# HTH-2019-Badge-PROD-RC1.net
KiCad netlist of a schematic drawn in EAGLE
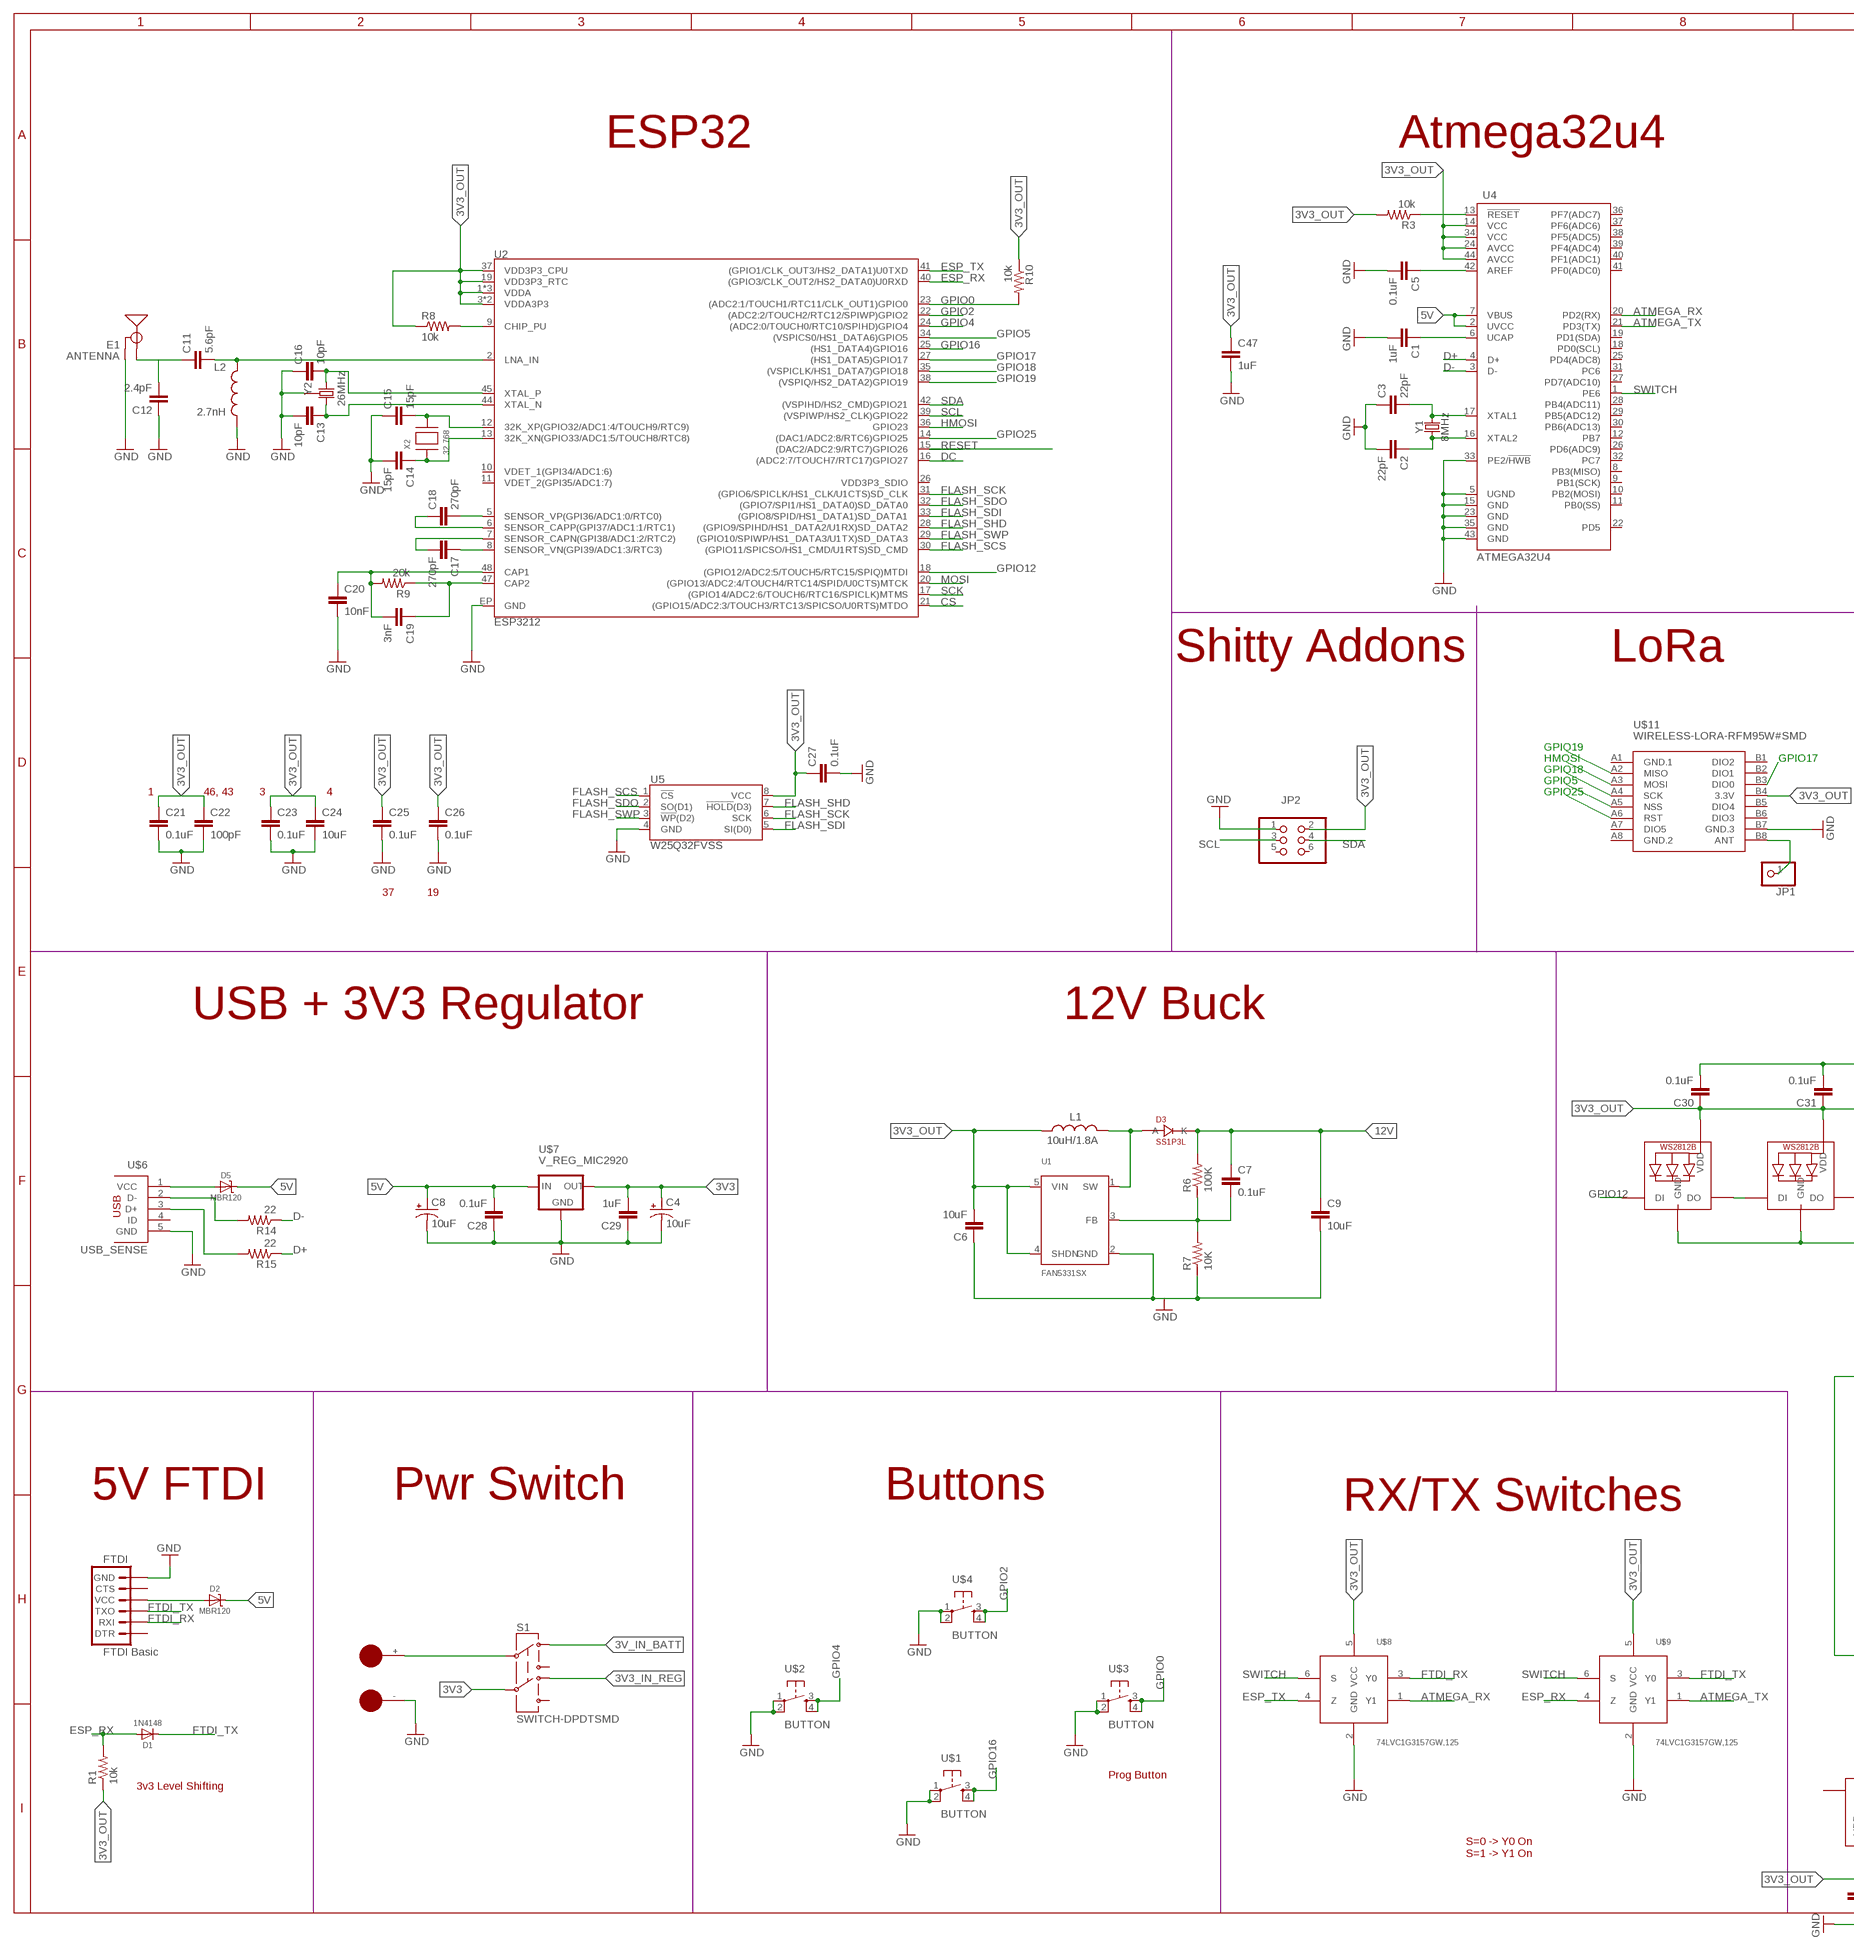
[diagram p0: schematic, sheet 1, part 1 of 2]
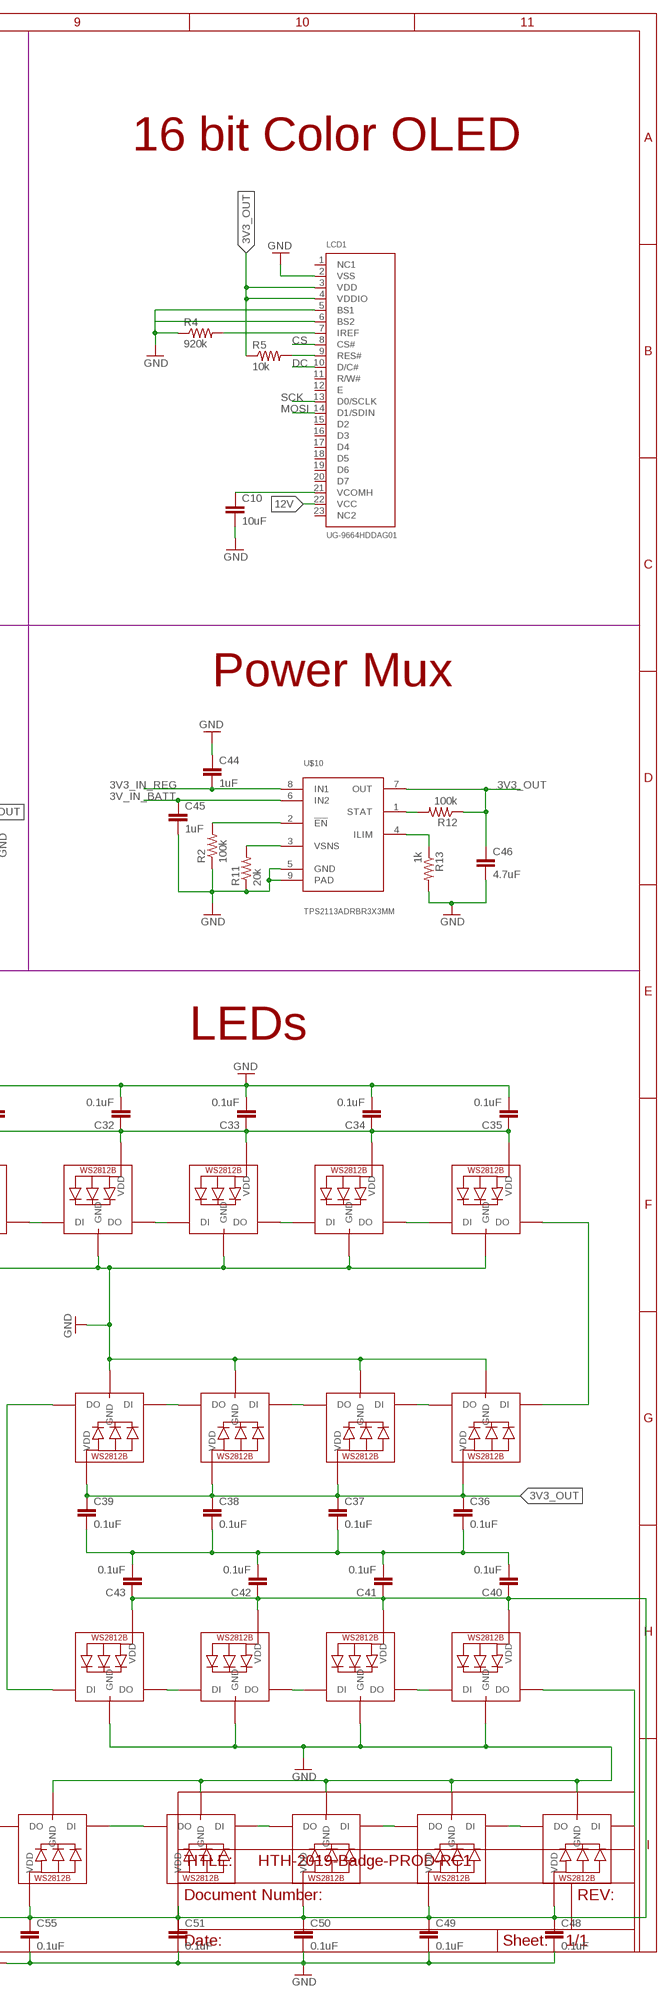
[diagram p1: schematic, sheet 1, part 2 of 2]

(export (version "E")
  (design (tool "Eeschema 10.0.6"))
  (components
    (comp (ref "C1")
      (value "1uF")
      (footprint "eagle-import:CAP0603")
      (libsource (lib "eagle-import") (part "CAP-0603-EMPTY-VALUES"))
    )
    (comp (ref "C2")
      (value "22pF")
      (footprint "eagle-import:CAP0603")
      (libsource (lib "eagle-import") (part "CAP-0603-EMPTY-VALUES"))
    )
    (comp (ref "C3")
      (value "22pF")
      (footprint "eagle-import:CAP0603")
      (libsource (lib "eagle-import") (part "CAP-0603-EMPTY-VALUES"))
    )
    (comp (ref "C4")
      (value "10uF")
      (footprint "eagle-import:EIA3216")
      (libsource (lib "eagle-import") (part "CAP_POL1206"))
    )
    (comp (ref "C5")
      (value "0.1uF")
      (footprint "eagle-import:CAP0603")
      (libsource (lib "eagle-import") (part "CAP-0603-EMPTY-VALUES"))
    )
    (comp (ref "C6")
      (value "10uF")
      (footprint "eagle-import:CAP0603")
      (fields (field (name "TOLERANCE") "10%") (field (name "VOLTAGE") "10V"))
      (libsource (lib "eagle-import") (part "CAP-0603-10UF-10V-10%"))
    )
    (comp (ref "C7")
      (value "0.1uF")
      (footprint "eagle-import:CAP0603")
      (fields (field (name "TOLERANCE") "10%") (field (name "VOLTAGE") "25V"))
      (libsource (lib "eagle-import") (part "CAP-0603-0.1UF-25V-10%"))
    )
    (comp (ref "C8")
      (value "10uF")
      (footprint "eagle-import:EIA3216")
      (libsource (lib "eagle-import") (part "CAP_POL1206"))
    )
    (comp (ref "C9")
      (value "10uF")
      (footprint "eagle-import:CAP0603")
      (fields (field (name "TOLERANCE") "20%") (field (name "VOLTAGE") "25V"))
      (libsource (lib "eagle-import") (part "CAP-0603-10UF-25V-20%"))
    )
    (comp (ref "C10")
      (value "10uF")
      (footprint "eagle-import:CAP0603")
      (libsource (lib "eagle-import") (part "CAP-0603-EMPTY-VALUES"))
    )
    (comp (ref "C11")
      (value "5.6pF")
      (footprint "eagle-import:CAP0603")
      (libsource (lib "eagle-import") (part "CAP-0603-EMPTY-VALUES"))
    )
    (comp (ref "C12")
      (value "2.4pF")
      (footprint "eagle-import:CAP0603")
      (libsource (lib "eagle-import") (part "CAP-0603-EMPTY-VALUES"))
    )
    (comp (ref "C13")
      (value "10pF")
      (footprint "eagle-import:CAP0603")
      (libsource (lib "eagle-import") (part "CAP-0603-EMPTY-VALUES"))
    )
    (comp (ref "C14")
      (value "15pF")
      (footprint "eagle-import:CAP0603")
      (libsource (lib "eagle-import") (part "CAP-0603-EMPTY-VALUES"))
    )
    (comp (ref "C15")
      (value "15pF")
      (footprint "eagle-import:CAP0603")
      (libsource (lib "eagle-import") (part "CAP-0603-EMPTY-VALUES"))
    )
    (comp (ref "C16")
      (value "10pF")
      (footprint "eagle-import:CAP0603")
      (libsource (lib "eagle-import") (part "CAP-0603-EMPTY-VALUES"))
    )
    (comp (ref "C17")
      (value "270pF")
      (footprint "eagle-import:CAP0603")
      (libsource (lib "eagle-import") (part "CAP-0603-EMPTY-VALUES"))
    )
    (comp (ref "C18")
      (value "270pF")
      (footprint "eagle-import:CAP0603")
      (libsource (lib "eagle-import") (part "CAP-0603-EMPTY-VALUES"))
    )
    (comp (ref "C19")
      (value "3nF")
      (footprint "eagle-import:CAP0603")
      (libsource (lib "eagle-import") (part "CAP-0603-EMPTY-VALUES"))
    )
    (comp (ref "C20")
      (value "10nF")
      (footprint "eagle-import:CAP0603")
      (libsource (lib "eagle-import") (part "CAP-0603-EMPTY-VALUES"))
    )
    (comp (ref "C21")
      (value "0.1uF")
      (footprint "eagle-import:CAP0603")
      (libsource (lib "eagle-import") (part "CAP-0603-EMPTY-VALUES"))
    )
    (comp (ref "C22")
      (value "100pF")
      (footprint "eagle-import:CAP0603")
      (libsource (lib "eagle-import") (part "CAP-0603-EMPTY-VALUES"))
    )
    (comp (ref "C23")
      (value "0.1uF")
      (footprint "eagle-import:CAP0603")
      (libsource (lib "eagle-import") (part "CAP-0603-EMPTY-VALUES"))
    )
    (comp (ref "C24")
      (value "10uF")
      (footprint "eagle-import:CAP0603")
      (libsource (lib "eagle-import") (part "CAP-0603-EMPTY-VALUES"))
    )
    (comp (ref "C25")
      (value "0.1uF")
      (footprint "eagle-import:CAP0603")
      (libsource (lib "eagle-import") (part "CAP-0603-EMPTY-VALUES"))
    )
    (comp (ref "C26")
      (value "0.1uF")
      (footprint "eagle-import:CAP0603")
      (libsource (lib "eagle-import") (part "CAP-0603-EMPTY-VALUES"))
    )
    (comp (ref "C27")
      (value "0.1uF")
      (footprint "eagle-import:CAP0603")
      (libsource (lib "eagle-import") (part "CAP-0603-EMPTY-VALUES"))
    )
    (comp (ref "C28")
      (value "0.1uF")
      (footprint "eagle-import:CAP0603")
      (libsource (lib "eagle-import") (part "CAP-0603-EMPTY-VALUES"))
    )
    (comp (ref "C29")
      (value "1uF")
      (footprint "eagle-import:CAP0603")
      (libsource (lib "eagle-import") (part "CAP-0603-EMPTY-VALUES"))
    )
    (comp (ref "C30")
      (value "0.1uF")
      (footprint "eagle-import:CAP0603")
      (libsource (lib "eagle-import") (part "CAP-0603-EMPTY-VALUES"))
    )
    (comp (ref "C31")
      (value "0.1uF")
      (footprint "eagle-import:CAP0603")
      (libsource (lib "eagle-import") (part "CAP-0603-EMPTY-VALUES"))
    )
    (comp (ref "C32")
      (value "0.1uF")
      (footprint "eagle-import:CAP0603")
      (libsource (lib "eagle-import") (part "CAP-0603-EMPTY-VALUES"))
    )
    (comp (ref "C33")
      (value "0.1uF")
      (footprint "eagle-import:CAP0603")
      (libsource (lib "eagle-import") (part "CAP-0603-EMPTY-VALUES"))
    )
    (comp (ref "C34")
      (value "0.1uF")
      (footprint "eagle-import:CAP0603")
      (libsource (lib "eagle-import") (part "CAP-0603-EMPTY-VALUES"))
    )
    (comp (ref "C35")
      (value "0.1uF")
      (footprint "eagle-import:CAP0603")
      (libsource (lib "eagle-import") (part "CAP-0603-EMPTY-VALUES"))
    )
    (comp (ref "C36")
      (value "0.1uF")
      (footprint "eagle-import:CAP0603")
      (libsource (lib "eagle-import") (part "CAP-0603-EMPTY-VALUES"))
    )
    (comp (ref "C37")
      (value "0.1uF")
      (footprint "eagle-import:CAP0603")
      (libsource (lib "eagle-import") (part "CAP-0603-EMPTY-VALUES"))
    )
    (comp (ref "C38")
      (value "0.1uF")
      (footprint "eagle-import:CAP0603")
      (libsource (lib "eagle-import") (part "CAP-0603-EMPTY-VALUES"))
    )
    (comp (ref "C39")
      (value "0.1uF")
      (footprint "eagle-import:CAP0603")
      (libsource (lib "eagle-import") (part "CAP-0603-EMPTY-VALUES"))
    )
    (comp (ref "C40")
      (value "0.1uF")
      (footprint "eagle-import:CAP0603")
      (libsource (lib "eagle-import") (part "CAP-0603-EMPTY-VALUES"))
    )
    (comp (ref "C41")
      (value "0.1uF")
      (footprint "eagle-import:CAP0603")
      (libsource (lib "eagle-import") (part "CAP-0603-EMPTY-VALUES"))
    )
    (comp (ref "C42")
      (value "0.1uF")
      (footprint "eagle-import:CAP0603")
      (libsource (lib "eagle-import") (part "CAP-0603-EMPTY-VALUES"))
    )
    (comp (ref "C43")
      (value "0.1uF")
      (footprint "eagle-import:CAP0603")
      (libsource (lib "eagle-import") (part "CAP-0603-EMPTY-VALUES"))
    )
    (comp (ref "C44")
      (value "1uF")
      (footprint "eagle-import:CAP0603")
      (libsource (lib "eagle-import") (part "CAP-0603-EMPTY-VALUES"))
    )
    (comp (ref "C45")
      (value "1uF")
      (footprint "eagle-import:CAP0603")
      (libsource (lib "eagle-import") (part "CAP-0603-EMPTY-VALUES"))
    )
    (comp (ref "C46")
      (value "4.7uF")
      (footprint "eagle-import:CAP0603")
      (libsource (lib "eagle-import") (part "CAP-0603-EMPTY-VALUES"))
    )
    (comp (ref "C47")
      (value "1uF")
      (footprint "eagle-import:CAP0603")
      (libsource (lib "eagle-import") (part "CAP-0603-EMPTY-VALUES"))
    )
    (comp (ref "C48")
      (value "0.1uF")
      (footprint "eagle-import:CAP0603")
      (libsource (lib "eagle-import") (part "CAP-0603-EMPTY-VALUES"))
    )
    (comp (ref "C49")
      (value "0.1uF")
      (footprint "eagle-import:CAP0603")
      (libsource (lib "eagle-import") (part "CAP-0603-EMPTY-VALUES"))
    )
    (comp (ref "C50")
      (value "0.1uF")
      (footprint "eagle-import:CAP0603")
      (libsource (lib "eagle-import") (part "CAP-0603-EMPTY-VALUES"))
    )
    (comp (ref "C51")
      (value "0.1uF")
      (footprint "eagle-import:CAP0603")
      (libsource (lib "eagle-import") (part "CAP-0603-EMPTY-VALUES"))
    )
    (comp (ref "C55")
      (value "0.1uF")
      (footprint "eagle-import:CAP0603")
      (libsource (lib "eagle-import") (part "CAP-0603-EMPTY-VALUES"))
    )
    (comp (ref "D1")
      (value "1N4148")
      (footprint "eagle-import:SOD-323")
      (libsource (lib "eagle-import") (part "DIODESOD-323"))
    )
    (comp (ref "D2")
      (value "MBR120")
      (footprint "eagle-import:SOD-123")
      (libsource (lib "eagle-import") (part "DIODE-SCHOTTKYSOD-123"))
    )
    (comp (ref "D3")
      (value "SS1P3L")
      (footprint "eagle-import:DO220AAL")
      (libsource (lib "eagle-import") (part "SS1P3L"))
    )
    (comp (ref "D5")
      (value "MBR120")
      (footprint "eagle-import:SOD-123")
      (libsource (lib "eagle-import") (part "DIODE-SCHOTTKYSOD-123"))
    )
    (comp (ref "E1")
      (value "ANTENNA")
      (footprint "eagle-import:TRACE_ANTENNA_2.4GHZ_25.7MM_TUNED")
      (libsource (lib "eagle-import") (part "ANTENNATRACE-TUNED"))
    )
    (comp (ref "FTDI")
      (value "FTDI Basic")
      (footprint "eagle-import:1X06")
      (libsource (lib "eagle-import") (part "ARDUINO_SERIAL_PROGRAMPTH"))
    )
    (comp (ref "JP1")
      (value "PINHD-1X1")
      (footprint "eagle-import:1X01")
      (libsource (lib "eagle-import") (part "PINHD-1X1"))
    )
    (comp (ref "JP2")
      (value "PINHD-2X3")
      (footprint "eagle-import:2X03")
      (libsource (lib "eagle-import") (part "PINHD-2X3"))
    )
    (comp (ref "L1")
      (value "10uH/1.8A")
      (footprint "eagle-import:SRU5028")
      (libsource (lib "eagle-import") (part "INDUCTORSRU5028"))
    )
    (comp (ref "L2")
      (value "2.7nH")
      (footprint "eagle-import:0603")
      (libsource (lib "eagle-import") (part "SparkFun-Passives_INDUCTOR0603"))
    )
    (comp (ref "LCD1")
      (value "UG-9664HDDAG01")
      (footprint "eagle-import:UG-9664HDDAG01_WRAPAROUND")
      (libsource (lib "eagle-import") (part "DISP_OLED_UG-9664HDDAG01WRAPAROUND"))
    )
    (comp (ref "LED1")
      (value "WS2812B3535")
      (footprint "eagle-import:LED3535")
      (libsource (lib "eagle-import") (part "WS2812B3535"))
    )
    (comp (ref "LED2")
      (value "WS2812B3535")
      (footprint "eagle-import:LED3535")
      (libsource (lib "eagle-import") (part "WS2812B3535"))
    )
    (comp (ref "LED3")
      (value "WS2812B3535")
      (footprint "eagle-import:LED3535")
      (libsource (lib "eagle-import") (part "WS2812B3535"))
    )
    (comp (ref "LED4")
      (value "WS2812B3535")
      (footprint "eagle-import:LED3535")
      (libsource (lib "eagle-import") (part "WS2812B3535"))
    )
    (comp (ref "LED5")
      (value "WS2812B3535")
      (footprint "eagle-import:LED3535")
      (libsource (lib "eagle-import") (part "WS2812B3535"))
    )
    (comp (ref "LED6")
      (value "WS2812B3535")
      (footprint "eagle-import:LED3535")
      (libsource (lib "eagle-import") (part "WS2812B3535"))
    )
    (comp (ref "LED7")
      (value "WS2812B3535")
      (footprint "eagle-import:LED3535")
      (libsource (lib "eagle-import") (part "WS2812B3535"))
    )
    (comp (ref "LED8")
      (value "WS2812B3535")
      (footprint "eagle-import:LED3535")
      (libsource (lib "eagle-import") (part "WS2812B3535"))
    )
    (comp (ref "LED9")
      (value "WS2812B3535")
      (footprint "eagle-import:LED3535")
      (libsource (lib "eagle-import") (part "WS2812B3535"))
    )
    (comp (ref "LED10")
      (value "WS2812B3535")
      (footprint "eagle-import:LED3535")
      (libsource (lib "eagle-import") (part "WS2812B3535"))
    )
    (comp (ref "LED11")
      (value "WS2812B3535")
      (footprint "eagle-import:LED3535")
      (libsource (lib "eagle-import") (part "WS2812B3535"))
    )
    (comp (ref "LED12")
      (value "WS2812B3535")
      (footprint "eagle-import:LED3535")
      (libsource (lib "eagle-import") (part "WS2812B3535"))
    )
    (comp (ref "LED13")
      (value "WS2812B3535")
      (footprint "eagle-import:LED3535")
      (libsource (lib "eagle-import") (part "WS2812B3535"))
    )
    (comp (ref "LED14")
      (value "WS2812B3535")
      (footprint "eagle-import:LED3535")
      (libsource (lib "eagle-import") (part "WS2812B3535"))
    )
    (comp (ref "LED15")
      (value "WS2812B3535")
      (footprint "eagle-import:LED3535")
      (libsource (lib "eagle-import") (part "WS2812B3535"))
    )
    (comp (ref "LED16")
      (value "WS2812B3535")
      (footprint "eagle-import:LED3535")
      (libsource (lib "eagle-import") (part "WS2812B3535"))
    )
    (comp (ref "LED17")
      (value "WS2812B3535")
      (footprint "eagle-import:LED3535")
      (libsource (lib "eagle-import") (part "WS2812B3535"))
    )
    (comp (ref "LED18")
      (value "WS2812B3535")
      (footprint "eagle-import:LED3535")
      (libsource (lib "eagle-import") (part "WS2812B3535"))
    )
    (comp (ref "LED19")
      (value "WS2812B3535")
      (footprint "eagle-import:LED3535")
      (libsource (lib "eagle-import") (part "WS2812B3535"))
    )
    (comp (ref "R1")
      (value "10k")
      (footprint "eagle-import:RES-0603")
      (libsource (lib "eagle-import") (part "RES-0603_EMPTY-FIELDS"))
    )
    (comp (ref "R2")
      (value "100k")
      (footprint "eagle-import:RES-0603")
      (libsource (lib "eagle-import") (part "RES-0603_EMPTY-FIELDS"))
    )
    (comp (ref "R3")
      (value "10k")
      (footprint "eagle-import:RES-0603")
      (libsource (lib "eagle-import") (part "RES-0603_EMPTY-FIELDS"))
    )
    (comp (ref "R4")
      (value "920k")
      (footprint "eagle-import:RES-0603")
      (libsource (lib "eagle-import") (part "RES-0603_EMPTY-FIELDS"))
    )
    (comp (ref "R5")
      (value "10k")
      (footprint "eagle-import:RES-0603")
      (libsource (lib "eagle-import") (part "RES-0603_EMPTY-FIELDS"))
    )
    (comp (ref "R6")
      (value "100K")
      (footprint "eagle-import:RES-0603")
      (fields (field (name "TOLERANCE") "5%"))
      (libsource (lib "eagle-import") (part "RES-0603-100K-5%"))
    )
    (comp (ref "R7")
      (value "10K")
      (footprint "eagle-import:RES-0603")
      (fields (field (name "TOLERANCE") "5%"))
      (libsource (lib "eagle-import") (part "RES-0603-10K-5%"))
    )
    (comp (ref "R8")
      (value "10k")
      (footprint "eagle-import:RES-0603")
      (libsource (lib "eagle-import") (part "RES-0603_EMPTY-FIELDS"))
    )
    (comp (ref "R9")
      (value "20k")
      (footprint "eagle-import:RES-0603")
      (libsource (lib "eagle-import") (part "RES-0603_EMPTY-FIELDS"))
    )
    (comp (ref "R10")
      (value "10k")
      (footprint "eagle-import:RES-0603")
      (libsource (lib "eagle-import") (part "RES-0603_EMPTY-FIELDS"))
    )
    (comp (ref "R11")
      (value "20k")
      (footprint "eagle-import:RES-0603")
      (libsource (lib "eagle-import") (part "RES-0603_EMPTY-FIELDS"))
    )
    (comp (ref "R12")
      (value "100k")
      (footprint "eagle-import:RES-0603")
      (libsource (lib "eagle-import") (part "RES-0603_EMPTY-FIELDS"))
    )
    (comp (ref "R13")
      (value "1k")
      (footprint "eagle-import:RES-0603")
      (libsource (lib "eagle-import") (part "RES-0603_EMPTY-FIELDS"))
    )
    (comp (ref "R14")
      (value "22")
      (footprint "eagle-import:RES-0603")
      (libsource (lib "eagle-import") (part "RES-0603_EMPTY-FIELDS"))
    )
    (comp (ref "R15")
      (value "22")
      (footprint "eagle-import:RES-0603")
      (libsource (lib "eagle-import") (part "RES-0603_EMPTY-FIELDS"))
    )
    (comp (ref "S1")
      (value "SWITCH-DPDTSMD")
      (footprint "eagle-import:AYZ0202")
      (libsource (lib "eagle-import") (part "SWITCH-DPDTSMD"))
    )
    (comp (ref "U$1")
      (value "BUTTON")
      (footprint "eagle-import:BUTTON")
      (libsource (lib "eagle-import") (part "BUTTON"))
    )
    (comp (ref "U$2")
      (value "BUTTON")
      (footprint "eagle-import:BUTTON")
      (libsource (lib "eagle-import") (part "BUTTON"))
    )
    (comp (ref "U$3")
      (value "BUTTON")
      (footprint "eagle-import:BUTTON")
      (libsource (lib "eagle-import") (part "BUTTON"))
    )
    (comp (ref "U$4")
      (value "BUTTON")
      (footprint "eagle-import:BUTTON")
      (libsource (lib "eagle-import") (part "BUTTON"))
    )
    (comp (ref "U$5")
      (value "BAT_HOLD")
      (footprint "eagle-import:AA")
      (libsource (lib "eagle-import") (part "BAT_HOLD"))
    )
    (comp (ref "U$6")
      (value "USB_SENSE")
      (footprint "eagle-import:USB-MICRO-TH-SUPPORT")
      (libsource (lib "eagle-import") (part "USB_SENSE"))
    )
    (comp (ref "U$7")
      (value "V_REG_MIC2920")
      (footprint "eagle-import:SOT223")
      (libsource (lib "eagle-import") (part "V_REG_MIC2920"))
    )
    (comp (ref "U$8")
      (value "74LVC1G3157GW,125")
      (footprint "eagle-import:SOT-363")
      (libsource (lib "eagle-import") (part "74LVC1G3157GW,125"))
    )
    (comp (ref "U$9")
      (value "74LVC1G3157GW,125")
      (footprint "eagle-import:SOT-363")
      (libsource (lib "eagle-import") (part "74LVC1G3157GW,125"))
    )
    (comp (ref "U$10")
      (value "TPS2113ADRBR3X3MM")
      (footprint "eagle-import:8-VDFN")
      (libsource (lib "eagle-import") (part "TPS2113ADRBR3X3MM"))
    )
    (comp (ref "U$11")
      (value "WIRELESS-LORA-RFM95W#SMD")
      (footprint "eagle-import:WIRELESS-LORA-RFM95W#SMD")
      (libsource (lib "eagle-import") (part "WIRELESS-LORA-RFM95W#SMD"))
    )
    (comp (ref "U1")
      (value "FAN5331SX")
      (footprint "eagle-import:SOT23-5")
      (libsource (lib "eagle-import") (part "FAN5331"))
    )
    (comp (ref "U2")
      (value "ESP3212")
      (footprint "eagle-import:QFN48-0.4MM")
      (libsource (lib "eagle-import") (part "ESP3212"))
    )
    (comp (ref "U4")
      (value "ATMEGA32U4")
      (footprint "eagle-import:QFN-44-NOPAD_1_1-OUTFAKES")
      (libsource (lib "eagle-import") (part "ATMEGA32U4OUTFAKES"))
    )
    (comp (ref "U5")
      (value "W25Q32FVSS")
      (footprint "eagle-import:SOIC-8")
      (libsource (lib "eagle-import") (part "W25Q32FVSS"))
    )
    (comp (ref "X2")
      (value "32.768")
      (footprint "eagle-import:XTAL3215")
      (libsource (lib "eagle-import") (part "XTAL-3.2X1.5"))
    )
    (comp (ref "Y1")
      (value "8MHz")
      (footprint "eagle-import:CRYSTAL-SMD-5X3.2-4PAD")
      (libsource (lib "eagle-import") (part "CRYSTAL-8MHZSMD-5X3.2"))
    )
    (comp (ref "Y2")
      (value "26MHz")
      (footprint "eagle-import:CRYSTAL-SMD-3.2X2.5")
      (libsource (lib "eagle-import") (part "CRYSTAL-GROUNDED3.2X2.5"))
    )
  )
  (nets
    (net (code "1") (name "/ATMEGA_RX") (class "Default")
      (node (ref "U$8") (pin "1") (pinfunction "Y1_1") (pintype "bidirectional"))
      (node (ref "U4") (pin "20") (pinfunction "PD2(RX)_20") (pintype "bidirectional"))
    )
    (net (code "2") (name "/ATMEGA_TX") (class "Default")
      (node (ref "U$9") (pin "1") (pinfunction "Y1_1") (pintype "bidirectional"))
      (node (ref "U4") (pin "21") (pinfunction "PD3(TX)_21") (pintype "bidirectional"))
    )
    (net (code "3") (name "/CS") (class "Default")
      (node (ref "LCD1") (pin "8") (pinfunction "CS#_8") (pintype "bidirectional"))
      (node (ref "U2") (pin "21") (pinfunction "(GPIO15/ADC2:3/TOUCH3/RTC13/SPICSO/U0RTS)MTDO_21") (pintype "bidirectional"))
    )
    (net (code "4") (name "/D+") (class "Default")
      (node (ref "R15") (pin "1") (pinfunction "1_1") (pintype "passive"))
      (node (ref "U4") (pin "4") (pinfunction "D+_4") (pintype "bidirectional"))
    )
    (net (code "5") (name "/D-") (class "Default")
      (node (ref "R14") (pin "1") (pinfunction "1_1") (pintype "passive"))
      (node (ref "U4") (pin "3") (pinfunction "D-_3") (pintype "bidirectional"))
    )
    (net (code "6") (name "/DC") (class "Default")
      (node (ref "LCD1") (pin "10") (pinfunction "D/C#_10") (pintype "bidirectional"))
      (node (ref "U2") (pin "16") (pinfunction "(ADC2:7/TOUCH7/RTC17)GPIO27_16") (pintype "bidirectional"))
    )
    (net (code "7") (name "/ESP_RX") (class "Default")
      (node (ref "D1") (pin "A") (pinfunction "A_A") (pintype "passive"))
      (node (ref "R1") (pin "2") (pinfunction "2_2") (pintype "passive"))
      (node (ref "U$9") (pin "4") (pinfunction "Z_4") (pintype "bidirectional"))
      (node (ref "U2") (pin "40") (pinfunction "(GPIO3/CLK_OUT2/HS2_DATA0)U0RXD_40") (pintype "bidirectional"))
    )
    (net (code "8") (name "/ESP_TX") (class "Default")
      (node (ref "U$8") (pin "4") (pinfunction "Z_4") (pintype "bidirectional"))
      (node (ref "U2") (pin "41") (pinfunction "(GPIO1/CLK_OUT3/HS2_DATA1)U0TXD_41") (pintype "bidirectional"))
    )
    (net (code "9") (name "/FLASH_SCK") (class "Default")
      (node (ref "U2") (pin "31") (pinfunction "(GPIO6/SPICLK/HS1_CLK/U1CTS)SD_CLK_31") (pintype "bidirectional"))
      (node (ref "U5") (pin "6") (pinfunction "SCK_6") (pintype "bidirectional"))
    )
    (net (code "10") (name "/FLASH_SCS") (class "Default")
      (node (ref "U2") (pin "30") (pinfunction "(GPIO11/SPICSO/HS1_CMD/U1RTS)SD_CMD_30") (pintype "bidirectional"))
      (node (ref "U5") (pin "1") (pinfunction "~{CS}_1") (pintype "bidirectional"))
    )
    (net (code "11") (name "/FLASH_SDI") (class "Default")
      (node (ref "U2") (pin "33") (pinfunction "(GPIO8/SPID/HS1_DATA1)SD_DATA1_33") (pintype "bidirectional"))
      (node (ref "U5") (pin "5") (pinfunction "SI(D0)_5") (pintype "bidirectional"))
    )
    (net (code "12") (name "/FLASH_SDO") (class "Default")
      (node (ref "U2") (pin "32") (pinfunction "(GPIO7/SPI1/HS1_DATA0)SD_DATA0_32") (pintype "bidirectional"))
      (node (ref "U5") (pin "2") (pinfunction "SO(D1)_2") (pintype "bidirectional"))
    )
    (net (code "13") (name "/FLASH_SHD") (class "Default")
      (node (ref "U2") (pin "28") (pinfunction "(GPIO9/SPIHD/HS1_DATA2/U1RX)SD_DATA2_28") (pintype "bidirectional"))
      (node (ref "U5") (pin "7") (pinfunction "~{HOLD}(D3)_7") (pintype "bidirectional"))
    )
    (net (code "14") (name "/FLASH_SWP") (class "Default")
      (node (ref "U2") (pin "29") (pinfunction "(GPIO10/SPIWP/HS1_DATA3/U1TX)SD_DATA3_29") (pintype "bidirectional"))
      (node (ref "U5") (pin "3") (pinfunction "~{WP}(D2)_3") (pintype "bidirectional"))
    )
    (net (code "15") (name "/FTDI_RX") (class "Default")
      (node (ref "FTDI") (pin "2") (pinfunction "RXI_2") (pintype "passive"))
      (node (ref "U$8") (pin "3") (pinfunction "Y0_3") (pintype "bidirectional"))
    )
    (net (code "16") (name "/FTDI_TX") (class "Default")
      (node (ref "D1") (pin "C") (pinfunction "C_C") (pintype "passive"))
      (node (ref "FTDI") (pin "3") (pinfunction "TXO_3") (pintype "passive"))
      (node (ref "U$9") (pin "3") (pinfunction "Y0_3") (pintype "bidirectional"))
    )
    (net (code "17") (name "/GND.1") (class "Default")
      (node (ref "U$11") (pin "A1") (pinfunction "GND.1_A1") (pintype "power_in"))
    )
    (net (code "18") (name "/GND.2") (class "Default")
      (node (ref "U$11") (pin "A8") (pinfunction "GND.2_A8") (pintype "power_in"))
    )
    (net (code "19") (name "/GPIO0") (class "Default")
      (node (ref "R10") (pin "2") (pinfunction "2_2") (pintype "passive"))
      (node (ref "U$3") (pin "3") (pinfunction "3_3") (pintype "passive"))
      (node (ref "U$3") (pin "4") (pinfunction "4_4") (pintype "passive"))
      (node (ref "U2") (pin "23") (pinfunction "(ADC2:1/TOUCH1/RTC11/CLK_OUT1)GPIO0_23") (pintype "bidirectional"))
    )
    (net (code "20") (name "/GPIO2") (class "Default")
      (node (ref "U$4") (pin "3") (pinfunction "3_3") (pintype "passive"))
      (node (ref "U$4") (pin "4") (pinfunction "4_4") (pintype "passive"))
      (node (ref "U2") (pin "22") (pinfunction "(ADC2:2/TOUCH2/RTC12/SPIWP)GPIO2_22") (pintype "bidirectional"))
    )
    (net (code "21") (name "/GPIO4") (class "Default")
      (node (ref "U$2") (pin "3") (pinfunction "3_3") (pintype "passive"))
      (node (ref "U$2") (pin "4") (pinfunction "4_4") (pintype "passive"))
      (node (ref "U2") (pin "24") (pinfunction "(ADC2:0/TOUCH0/RTC10/SPIHD)GPIO4_24") (pintype "bidirectional"))
    )
    (net (code "22") (name "/GPIO5") (class "Default")
      (node (ref "U$11") (pin "A5") (pinfunction "NSS_A5") (pintype "bidirectional"))
      (node (ref "U2") (pin "34") (pinfunction "(VSPICS0/HS1_DATA6)GPIO5_34") (pintype "bidirectional"))
    )
    (net (code "23") (name "/GPIO12") (class "Default")
      (node (ref "LED5") (pin "1") (pinfunction "DI_1") (pintype "input"))
      (node (ref "U2") (pin "18") (pinfunction "(GPIO12/ADC2:5/TOUCH5/RTC15/SPIQ)MTDI_18") (pintype "bidirectional"))
    )
    (net (code "24") (name "/GPIO16") (class "Default")
      (node (ref "U$1") (pin "3") (pinfunction "3_3") (pintype "passive"))
      (node (ref "U$1") (pin "4") (pinfunction "4_4") (pintype "passive"))
      (node (ref "U2") (pin "25") (pinfunction "(HS1_DATA4)GPIO16_25") (pintype "bidirectional"))
    )
    (net (code "25") (name "/GPIO17") (class "Default")
      (node (ref "U$11") (pin "B3") (pinfunction "DIO0_B3") (pintype "bidirectional"))
      (node (ref "U2") (pin "27") (pinfunction "(HS1_DATA5)GPIO17_27") (pintype "bidirectional"))
    )
    (net (code "26") (name "/GPIO18") (class "Default")
      (node (ref "U$11") (pin "A4") (pinfunction "SCK_A4") (pintype "bidirectional"))
      (node (ref "U2") (pin "35") (pinfunction "(VSPICLK/HS1_DATA7)GPIO18_35") (pintype "bidirectional"))
    )
    (net (code "27") (name "/GPIO19") (class "Default")
      (node (ref "U$11") (pin "A2") (pinfunction "MISO_A2") (pintype "bidirectional"))
      (node (ref "U2") (pin "38") (pinfunction "(VSPIQ/HS2_DATA2)GPIO19_38") (pintype "bidirectional"))
    )
    (net (code "28") (name "/GPIO25") (class "Default")
      (node (ref "U$11") (pin "A6") (pinfunction "RST_A6") (pintype "bidirectional"))
      (node (ref "U2") (pin "14") (pinfunction "(DAC1/ADC2:8/RTC6)GPIO25_14") (pintype "bidirectional"))
    )
    (net (code "29") (name "/HMOSI") (class "Default")
      (node (ref "U$11") (pin "A3") (pinfunction "MOSI_A3") (pintype "bidirectional"))
      (node (ref "U2") (pin "36") (pinfunction "GPIO23_36") (pintype "bidirectional"))
    )
    (net (code "30") (name "/MOSI") (class "Default")
      (node (ref "LCD1") (pin "14") (pinfunction "D1/SDIN_14") (pintype "bidirectional"))
      (node (ref "U2") (pin "20") (pinfunction "(GPIO13/ADC2:4/TOUCH4/RTC14/SPID/U0CTS)MTCK_20") (pintype "bidirectional"))
    )
    (net (code "31") (name "/RESET") (class "Default")
      (node (ref "LCD1") (pin "9") (pinfunction "RES#_9") (pintype "bidirectional"))
      (node (ref "R5") (pin "2") (pinfunction "2_2") (pintype "passive"))
      (node (ref "U2") (pin "15") (pinfunction "(DAC2/ADC2:9/RTC7)GPIO26_15") (pintype "bidirectional"))
    )
    (net (code "32") (name "/SCK") (class "Default")
      (node (ref "LCD1") (pin "13") (pinfunction "D0/SCLK_13") (pintype "bidirectional"))
      (node (ref "U2") (pin "17") (pinfunction "(GPIO14/ADC2:6/TOUCH6/RTC16/SPICLK)MTMS_17") (pintype "bidirectional"))
    )
    (net (code "33") (name "/SCL") (class "Default")
      (node (ref "JP2") (pin "3") (pinfunction "3_3") (pintype "passive"))
      (node (ref "U2") (pin "39") (pinfunction "(VSPIWP/HS2_CLK)GPIO22_39") (pintype "bidirectional"))
    )
    (net (code "34") (name "/SDA") (class "Default")
      (node (ref "JP2") (pin "4") (pinfunction "4_4") (pintype "passive"))
      (node (ref "U2") (pin "42") (pinfunction "(VSPIHD/HS2_CMD)GPIO21_42") (pintype "bidirectional"))
    )
    (net (code "35") (name "/SWITCH") (class "Default")
      (node (ref "U$8") (pin "6") (pinfunction "S_6") (pintype "bidirectional"))
      (node (ref "U$9") (pin "6") (pinfunction "S_6") (pintype "bidirectional"))
      (node (ref "U4") (pin "1") (pinfunction "PE6_1") (pintype "bidirectional"))
    )
    (net (code "36") (name "3V3") (class "Default")
      (node (ref "C29") (pin "2") (pinfunction "2_2") (pintype "passive"))
      (node (ref "C4") (pin "A") (pinfunction "+_A") (pintype "passive"))
      (node (ref "S1") (pin "5") (pinfunction "5_5") (pintype "bidirectional"))
      (node (ref "U$7") (pin "3") (pinfunction "OUT_3") (pintype "output"))
    )
    (net (code "37") (name "3V3_IN_REG") (class "Default")
      (node (ref "C44") (pin "2") (pinfunction "2_2") (pintype "passive"))
      (node (ref "S1") (pin "4") (pinfunction "4_4") (pintype "bidirectional"))
      (node (ref "U$10") (pin "8") (pinfunction "IN1_8") (pintype "bidirectional"))
    )
    (net (code "38") (name "3V3_OUT") (class "Default")
      (node (ref "C21") (pin "1") (pinfunction "1_1") (pintype "passive"))
      (node (ref "C22") (pin "1") (pinfunction "1_1") (pintype "passive"))
      (node (ref "C23") (pin "1") (pinfunction "1_1") (pintype "passive"))
      (node (ref "C24") (pin "1") (pinfunction "1_1") (pintype "passive"))
      (node (ref "C25") (pin "1") (pinfunction "1_1") (pintype "passive"))
      (node (ref "C26") (pin "1") (pinfunction "1_1") (pintype "passive"))
      (node (ref "C27") (pin "1") (pinfunction "1_1") (pintype "passive"))
      (node (ref "C30") (pin "1") (pinfunction "1_1") (pintype "passive"))
      (node (ref "C31") (pin "1") (pinfunction "1_1") (pintype "passive"))
      (node (ref "C32") (pin "1") (pinfunction "1_1") (pintype "passive"))
      (node (ref "C33") (pin "1") (pinfunction "1_1") (pintype "passive"))
      (node (ref "C34") (pin "1") (pinfunction "1_1") (pintype "passive"))
      (node (ref "C35") (pin "1") (pinfunction "1_1") (pintype "passive"))
      (node (ref "C36") (pin "1") (pinfunction "1_1") (pintype "passive"))
      (node (ref "C37") (pin "1") (pinfunction "1_1") (pintype "passive"))
      (node (ref "C38") (pin "1") (pinfunction "1_1") (pintype "passive"))
      (node (ref "C39") (pin "1") (pinfunction "1_1") (pintype "passive"))
      (node (ref "C40") (pin "1") (pinfunction "1_1") (pintype "passive"))
      (node (ref "C41") (pin "1") (pinfunction "1_1") (pintype "passive"))
      (node (ref "C42") (pin "1") (pinfunction "1_1") (pintype "passive"))
      (node (ref "C43") (pin "1") (pinfunction "1_1") (pintype "passive"))
      (node (ref "C46") (pin "1") (pinfunction "1_1") (pintype "passive"))
      (node (ref "C47") (pin "1") (pinfunction "1_1") (pintype "passive"))
      (node (ref "C48") (pin "1") (pinfunction "1_1") (pintype "passive"))
      (node (ref "C49") (pin "1") (pinfunction "1_1") (pintype "passive"))
      (node (ref "C50") (pin "1") (pinfunction "1_1") (pintype "passive"))
      (node (ref "C51") (pin "1") (pinfunction "1_1") (pintype "passive"))
      (node (ref "C55") (pin "1") (pinfunction "1_1") (pintype "passive"))
      (node (ref "C6") (pin "2") (pinfunction "2_2") (pintype "passive"))
      (node (ref "JP2") (pin "2") (pinfunction "2_2") (pintype "passive"))
      (node (ref "L1") (pin "1") (pinfunction "1_1") (pintype "passive"))
      (node (ref "LCD1") (pin "3") (pinfunction "VDD_3") (pintype "bidirectional"))
      (node (ref "LCD1") (pin "4") (pinfunction "VDDIO_4") (pintype "bidirectional"))
      (node (ref "LED1") (pin "2") (pinfunction "VDD_2") (pintype "power_in"))
      (node (ref "LED10") (pin "2") (pinfunction "VDD_2") (pintype "power_in"))
      (node (ref "LED11") (pin "2") (pinfunction "VDD_2") (pintype "power_in"))
      (node (ref "LED12") (pin "2") (pinfunction "VDD_2") (pintype "power_in"))
      (node (ref "LED13") (pin "2") (pinfunction "VDD_2") (pintype "power_in"))
      (node (ref "LED14") (pin "2") (pinfunction "VDD_2") (pintype "power_in"))
      (node (ref "LED15") (pin "2") (pinfunction "VDD_2") (pintype "power_in"))
      (node (ref "LED16") (pin "2") (pinfunction "VDD_2") (pintype "power_in"))
      (node (ref "LED17") (pin "2") (pinfunction "VDD_2") (pintype "power_in"))
      (node (ref "LED18") (pin "2") (pinfunction "VDD_2") (pintype "power_in"))
      (node (ref "LED19") (pin "2") (pinfunction "VDD_2") (pintype "power_in"))
      (node (ref "LED2") (pin "2") (pinfunction "VDD_2") (pintype "power_in"))
      (node (ref "LED3") (pin "2") (pinfunction "VDD_2") (pintype "power_in"))
      (node (ref "LED4") (pin "2") (pinfunction "VDD_2") (pintype "power_in"))
      (node (ref "LED5") (pin "2") (pinfunction "VDD_2") (pintype "power_in"))
      (node (ref "LED6") (pin "2") (pinfunction "VDD_2") (pintype "power_in"))
      (node (ref "LED7") (pin "2") (pinfunction "VDD_2") (pintype "power_in"))
      (node (ref "LED8") (pin "2") (pinfunction "VDD_2") (pintype "power_in"))
      (node (ref "LED9") (pin "2") (pinfunction "VDD_2") (pintype "power_in"))
      (node (ref "R1") (pin "1") (pinfunction "1_1") (pintype "passive"))
      (node (ref "R10") (pin "1") (pinfunction "1_1") (pintype "passive"))
      (node (ref "R12") (pin "1") (pinfunction "1_1") (pintype "passive"))
      (node (ref "R3") (pin "2") (pinfunction "2_2") (pintype "passive"))
      (node (ref "R5") (pin "1") (pinfunction "1_1") (pintype "passive"))
      (node (ref "R8") (pin "1") (pinfunction "1_1") (pintype "passive"))
      (node (ref "U$10") (pin "7") (pinfunction "OUT_7") (pintype "bidirectional"))
      (node (ref "U$11") (pin "B4") (pinfunction "3.3V_B4") (pintype "power_in"))
      (node (ref "U$8") (pin "5") (pinfunction "VCC_5") (pintype "bidirectional"))
      (node (ref "U$9") (pin "5") (pinfunction "VCC_5") (pintype "bidirectional"))
      (node (ref "U1") (pin "4") (pinfunction "SHDN_4") (pintype "bidirectional"))
      (node (ref "U1") (pin "5") (pinfunction "VIN_5") (pintype "bidirectional"))
      (node (ref "U2") (pin "1") (pinfunction "VDDA_1") (pintype "bidirectional"))
      (node (ref "U2") (pin "19") (pinfunction "VDD3P3_RTC_19") (pintype "bidirectional"))
      (node (ref "U2") (pin "3") (pinfunction "VDDA3P3_3") (pintype "bidirectional"))
      (node (ref "U2") (pin "37") (pinfunction "VDD3P3_CPU_37") (pintype "bidirectional"))
      (node (ref "U2") (pin "4") (pinfunction "VDDA3P3_4") (pintype "bidirectional"))
      (node (ref "U2") (pin "43") (pinfunction "VDDA_43") (pintype "bidirectional"))
      (node (ref "U2") (pin "46") (pinfunction "VDDA_46") (pintype "bidirectional"))
      (node (ref "U4") (pin "14") (pinfunction "VCC_14") (pintype "bidirectional"))
      (node (ref "U4") (pin "24") (pinfunction "AVCC_24") (pintype "bidirectional"))
      (node (ref "U4") (pin "34") (pinfunction "VCC_34") (pintype "bidirectional"))
      (node (ref "U4") (pin "44") (pinfunction "AVCC_44") (pintype "bidirectional"))
      (node (ref "U5") (pin "8") (pinfunction "VCC_8") (pintype "bidirectional"))
    )
    (net (code "39") (name "3V_IN_BATT") (class "Default")
      (node (ref "C45") (pin "1") (pinfunction "1_1") (pintype "passive"))
      (node (ref "S1") (pin "1") (pinfunction "1_1") (pintype "bidirectional"))
      (node (ref "U$10") (pin "6") (pinfunction "IN2_6") (pintype "bidirectional"))
    )
    (net (code "40") (name "5V") (class "Default")
      (node (ref "C28") (pin "2") (pinfunction "2_2") (pintype "passive"))
      (node (ref "C8") (pin "A") (pinfunction "+_A") (pintype "passive"))
      (node (ref "D2") (pin "C") (pinfunction "C_C") (pintype "passive"))
      (node (ref "D5") (pin "C") (pinfunction "C_C") (pintype "passive"))
      (node (ref "U$7") (pin "1") (pinfunction "IN_1") (pintype "input"))
      (node (ref "U4") (pin "2") (pinfunction "UVCC_2") (pintype "bidirectional"))
      (node (ref "U4") (pin "7") (pinfunction "VBUS_7") (pintype "bidirectional"))
    )
    (net (code "41") (name "12V") (class "Default")
      (node (ref "C7") (pin "1") (pinfunction "1_1") (pintype "passive"))
      (node (ref "C9") (pin "1") (pinfunction "1_1") (pintype "passive"))
      (node (ref "D3") (pin "P$1") (pinfunction "K_P$1") (pintype "bidirectional"))
      (node (ref "LCD1") (pin "22") (pinfunction "VCC_22") (pintype "bidirectional"))
      (node (ref "R6") (pin "2") (pinfunction "2_2") (pintype "passive"))
    )
    (net (code "42") (name "GND") (class "Default")
      (node (ref "C1") (pin "2") (pinfunction "2_2") (pintype "passive"))
      (node (ref "C10") (pin "2") (pinfunction "2_2") (pintype "passive"))
      (node (ref "C12") (pin "1") (pinfunction "1_1") (pintype "passive"))
      (node (ref "C13") (pin "2") (pinfunction "2_2") (pintype "passive"))
      (node (ref "C14") (pin "2") (pinfunction "2_2") (pintype "passive"))
      (node (ref "C15") (pin "1") (pinfunction "1_1") (pintype "passive"))
      (node (ref "C16") (pin "1") (pinfunction "1_1") (pintype "passive"))
      (node (ref "C2") (pin "2") (pinfunction "2_2") (pintype "passive"))
      (node (ref "C20") (pin "2") (pinfunction "2_2") (pintype "passive"))
      (node (ref "C21") (pin "2") (pinfunction "2_2") (pintype "passive"))
      (node (ref "C22") (pin "2") (pinfunction "2_2") (pintype "passive"))
      (node (ref "C23") (pin "2") (pinfunction "2_2") (pintype "passive"))
      (node (ref "C24") (pin "2") (pinfunction "2_2") (pintype "passive"))
      (node (ref "C25") (pin "2") (pinfunction "2_2") (pintype "passive"))
      (node (ref "C26") (pin "2") (pinfunction "2_2") (pintype "passive"))
      (node (ref "C27") (pin "2") (pinfunction "2_2") (pintype "passive"))
      (node (ref "C28") (pin "1") (pinfunction "1_1") (pintype "passive"))
      (node (ref "C29") (pin "1") (pinfunction "1_1") (pintype "passive"))
      (node (ref "C3") (pin "1") (pinfunction "1_1") (pintype "passive"))
      (node (ref "C30") (pin "2") (pinfunction "2_2") (pintype "passive"))
      (node (ref "C31") (pin "2") (pinfunction "2_2") (pintype "passive"))
      (node (ref "C32") (pin "2") (pinfunction "2_2") (pintype "passive"))
      (node (ref "C33") (pin "2") (pinfunction "2_2") (pintype "passive"))
      (node (ref "C34") (pin "2") (pinfunction "2_2") (pintype "passive"))
      (node (ref "C35") (pin "2") (pinfunction "2_2") (pintype "passive"))
      (node (ref "C4") (pin "C") (pinfunction "-_C") (pintype "passive"))
      (node (ref "C44") (pin "1") (pinfunction "1_1") (pintype "passive"))
      (node (ref "C45") (pin "2") (pinfunction "2_2") (pintype "passive"))
      (node (ref "C46") (pin "2") (pinfunction "2_2") (pintype "passive"))
      (node (ref "C47") (pin "2") (pinfunction "2_2") (pintype "passive"))
      (node (ref "C48") (pin "2") (pinfunction "2_2") (pintype "passive"))
      (node (ref "C49") (pin "2") (pinfunction "2_2") (pintype "passive"))
      (node (ref "C5") (pin "2") (pinfunction "2_2") (pintype "passive"))
      (node (ref "C50") (pin "2") (pinfunction "2_2") (pintype "passive"))
      (node (ref "C51") (pin "2") (pinfunction "2_2") (pintype "passive"))
      (node (ref "C55") (pin "2") (pinfunction "2_2") (pintype "passive"))
      (node (ref "C6") (pin "1") (pinfunction "1_1") (pintype "passive"))
      (node (ref "C8") (pin "C") (pinfunction "-_C") (pintype "passive"))
      (node (ref "C9") (pin "2") (pinfunction "2_2") (pintype "passive"))
      (node (ref "E1") (pin "GND") (pinfunction "GND_GND") (pintype "bidirectional"))
      (node (ref "E1") (pin "GND2") (pinfunction "GND_GND2") (pintype "bidirectional"))
      (node (ref "FTDI") (pin "6") (pinfunction "GND_6") (pintype "passive"))
      (node (ref "JP2") (pin "1") (pinfunction "1_1") (pintype "passive"))
      (node (ref "L2") (pin "2") (pinfunction "2_2") (pintype "passive"))
      (node (ref "LCD1") (pin "2") (pinfunction "VSS_2") (pintype "bidirectional"))
      (node (ref "LCD1") (pin "5") (pinfunction "BS1_5") (pintype "bidirectional"))
      (node (ref "LED1") (pin "4") (pinfunction "GND_4") (pintype "power_in"))
      (node (ref "LED10") (pin "4") (pinfunction "GND_4") (pintype "power_in"))
      (node (ref "LED11") (pin "4") (pinfunction "GND_4") (pintype "power_in"))
      (node (ref "LED12") (pin "4") (pinfunction "GND_4") (pintype "power_in"))
      (node (ref "LED13") (pin "4") (pinfunction "GND_4") (pintype "power_in"))
      (node (ref "LED14") (pin "4") (pinfunction "GND_4") (pintype "power_in"))
      (node (ref "LED15") (pin "4") (pinfunction "GND_4") (pintype "power_in"))
      (node (ref "LED16") (pin "4") (pinfunction "GND_4") (pintype "power_in"))
      (node (ref "LED17") (pin "4") (pinfunction "GND_4") (pintype "power_in"))
      (node (ref "LED18") (pin "4") (pinfunction "GND_4") (pintype "power_in"))
      (node (ref "LED19") (pin "4") (pinfunction "GND_4") (pintype "power_in"))
      (node (ref "LED2") (pin "4") (pinfunction "GND_4") (pintype "power_in"))
      (node (ref "LED3") (pin "4") (pinfunction "GND_4") (pintype "power_in"))
      (node (ref "LED4") (pin "4") (pinfunction "GND_4") (pintype "power_in"))
      (node (ref "LED5") (pin "4") (pinfunction "GND_4") (pintype "power_in"))
      (node (ref "LED6") (pin "4") (pinfunction "GND_4") (pintype "power_in"))
      (node (ref "LED7") (pin "4") (pinfunction "GND_4") (pintype "power_in"))
      (node (ref "LED8") (pin "4") (pinfunction "GND_4") (pintype "power_in"))
      (node (ref "LED9") (pin "4") (pinfunction "GND_4") (pintype "power_in"))
      (node (ref "R11") (pin "1") (pinfunction "1_1") (pintype "passive"))
      (node (ref "R13") (pin "2") (pinfunction "2_2") (pintype "passive"))
      (node (ref "R2") (pin "1") (pinfunction "1_1") (pintype "passive"))
      (node (ref "R4") (pin "1") (pinfunction "1_1") (pintype "passive"))
      (node (ref "R7") (pin "1") (pinfunction "1_1") (pintype "passive"))
      (node (ref "U$1") (pin "1") (pinfunction "1_1") (pintype "passive"))
      (node (ref "U$1") (pin "2") (pinfunction "2_2") (pintype "passive"))
      (node (ref "U$10") (pin "5") (pinfunction "GND_5") (pintype "bidirectional"))
      (node (ref "U$10") (pin "9") (pinfunction "PAD_9") (pintype "bidirectional"))
      (node (ref "U$11") (pin "B7") (pinfunction "GND.3_B7") (pintype "power_in"))
      (node (ref "U$2") (pin "1") (pinfunction "1_1") (pintype "passive"))
      (node (ref "U$2") (pin "2") (pinfunction "2_2") (pintype "passive"))
      (node (ref "U$3") (pin "1") (pinfunction "1_1") (pintype "passive"))
      (node (ref "U$3") (pin "2") (pinfunction "2_2") (pintype "passive"))
      (node (ref "U$4") (pin "1") (pinfunction "1_1") (pintype "passive"))
      (node (ref "U$4") (pin "2") (pinfunction "2_2") (pintype "passive"))
      (node (ref "U$5") (pin "-") (pinfunction "-_-") (pintype "bidirectional"))
      (node (ref "U$6") (pin "5") (pinfunction "GND_5") (pintype "bidirectional"))
      (node (ref "U$7") (pin "2") (pinfunction "GND_2") (pintype "input"))
      (node (ref "U$7") (pin "4") (pinfunction "GND_4") (pintype "input"))
      (node (ref "U$8") (pin "2") (pinfunction "GND_2") (pintype "bidirectional"))
      (node (ref "U$9") (pin "2") (pinfunction "GND_2") (pintype "bidirectional"))
      (node (ref "U1") (pin "2") (pinfunction "GND_2") (pintype "bidirectional"))
      (node (ref "U2") (pin "EP") (pinfunction "GND_EP") (pintype "bidirectional"))
      (node (ref "U4") (pin "15") (pinfunction "GND_15") (pintype "bidirectional"))
      (node (ref "U4") (pin "23") (pinfunction "GND_23") (pintype "bidirectional"))
      (node (ref "U4") (pin "33") (pinfunction "PE2/~{HWB}_33") (pintype "bidirectional"))
      (node (ref "U4") (pin "35") (pinfunction "GND_35") (pintype "bidirectional"))
      (node (ref "U4") (pin "43") (pinfunction "GND_43") (pintype "bidirectional"))
      (node (ref "U4") (pin "5") (pinfunction "UGND_5") (pintype "bidirectional"))
      (node (ref "U5") (pin "4") (pinfunction "GND_4") (pintype "bidirectional"))
      (node (ref "Y2") (pin "2") (pinfunction "GND_2") (pintype "passive"))
      (node (ref "Y2") (pin "4") (pinfunction "GND_4") (pintype "passive"))
    )
    (net (code "43") (name "Net-(C36-Pad2)") (class "Default")
      (node (ref "C36") (pin "2") (pinfunction "2_2") (pintype "passive"))
      (node (ref "C37") (pin "2") (pinfunction "2_2") (pintype "passive"))
      (node (ref "C38") (pin "2") (pinfunction "2_2") (pintype "passive"))
      (node (ref "C39") (pin "2") (pinfunction "2_2") (pintype "passive"))
      (node (ref "C40") (pin "2") (pinfunction "2_2") (pintype "passive"))
      (node (ref "C41") (pin "2") (pinfunction "2_2") (pintype "passive"))
      (node (ref "C42") (pin "2") (pinfunction "2_2") (pintype "passive"))
      (node (ref "C43") (pin "2") (pinfunction "2_2") (pintype "passive"))
    )
    (net (code "44") (name "Net-(D3-A)") (class "Default")
      (node (ref "D3") (pin "P$2") (pinfunction "A_P$2") (pintype "bidirectional"))
      (node (ref "L1") (pin "2") (pinfunction "2_2") (pintype "passive"))
      (node (ref "U1") (pin "1") (pinfunction "SW_1") (pintype "bidirectional"))
    )
    (net (code "45") (name "Net-(E1-SIGNAL)") (class "Default")
      (node (ref "C11") (pin "1") (pinfunction "1_1") (pintype "passive"))
      (node (ref "C12") (pin "2") (pinfunction "2_2") (pintype "passive"))
      (node (ref "E1") (pin "ANT") (pinfunction "SIGNAL_ANT") (pintype "bidirectional"))
    )
    (net (code "46") (name "Net-(FTDI-VCC)") (class "Default")
      (node (ref "D2") (pin "A") (pinfunction "A_A") (pintype "passive"))
      (node (ref "FTDI") (pin "4") (pinfunction "VCC_4") (pintype "passive"))
    )
    (net (code "47") (name "Net-(LCD1-IREF)") (class "Default")
      (node (ref "LCD1") (pin "7") (pinfunction "IREF_7") (pintype "bidirectional"))
      (node (ref "R4") (pin "2") (pinfunction "2_2") (pintype "passive"))
    )
    (net (code "48") (name "Net-(LCD1-VCOMH)") (class "Default")
      (node (ref "C10") (pin "1") (pinfunction "1_1") (pintype "passive"))
      (node (ref "LCD1") (pin "21") (pinfunction "VCOMH_21") (pintype "bidirectional"))
    )
    (net (code "49") (name "Net-(LED1-DI)") (class "Default")
      (node (ref "LED1") (pin "1") (pinfunction "DI_1") (pintype "input"))
      (node (ref "LED14") (pin "3") (pinfunction "DO_3") (pintype "output"))
    )
    (net (code "50") (name "Net-(LED1-DO)") (class "Default")
      (node (ref "LED1") (pin "3") (pinfunction "DO_3") (pintype "output"))
      (node (ref "LED2") (pin "1") (pinfunction "DI_1") (pintype "input"))
    )
    (net (code "51") (name "Net-(LED2-DO)") (class "Default")
      (node (ref "LED2") (pin "3") (pinfunction "DO_3") (pintype "output"))
      (node (ref "LED3") (pin "1") (pinfunction "DI_1") (pintype "input"))
    )
    (net (code "52") (name "Net-(LED3-DO)") (class "Default")
      (node (ref "LED3") (pin "3") (pinfunction "DO_3") (pintype "output"))
      (node (ref "LED4") (pin "1") (pinfunction "DI_1") (pintype "input"))
    )
    (net (code "53") (name "Net-(LED5-DO)") (class "Default")
      (node (ref "LED5") (pin "3") (pinfunction "DO_3") (pintype "output"))
      (node (ref "LED6") (pin "1") (pinfunction "DI_1") (pintype "input"))
    )
    (net (code "54") (name "Net-(LED6-DO)") (class "Default")
      (node (ref "LED6") (pin "3") (pinfunction "DO_3") (pintype "output"))
      (node (ref "LED7") (pin "1") (pinfunction "DI_1") (pintype "input"))
    )
    (net (code "55") (name "Net-(LED7-DO)") (class "Default")
      (node (ref "LED7") (pin "3") (pinfunction "DO_3") (pintype "output"))
      (node (ref "LED8") (pin "1") (pinfunction "DI_1") (pintype "input"))
    )
    (net (code "56") (name "Net-(LED8-DO)") (class "Default")
      (node (ref "LED8") (pin "3") (pinfunction "DO_3") (pintype "output"))
      (node (ref "LED9") (pin "1") (pinfunction "DI_1") (pintype "input"))
    )
    (net (code "57") (name "Net-(LED10-DI)") (class "Default")
      (node (ref "LED10") (pin "1") (pinfunction "DI_1") (pintype "input"))
      (node (ref "LED13") (pin "3") (pinfunction "DO_3") (pintype "output"))
    )
    (net (code "58") (name "Net-(LED10-DO)") (class "Default")
      (node (ref "LED10") (pin "3") (pinfunction "DO_3") (pintype "output"))
      (node (ref "LED12") (pin "1") (pinfunction "DI_1") (pintype "input"))
    )
    (net (code "59") (name "Net-(LED11-DI)") (class "Default")
      (node (ref "LED11") (pin "1") (pinfunction "DI_1") (pintype "input"))
      (node (ref "LED9") (pin "3") (pinfunction "DO_3") (pintype "output"))
    )
    (net (code "60") (name "Net-(LED11-DO)") (class "Default")
      (node (ref "LED11") (pin "3") (pinfunction "DO_3") (pintype "output"))
      (node (ref "LED13") (pin "1") (pinfunction "DI_1") (pintype "input"))
    )
    (net (code "61") (name "Net-(LED12-DO)") (class "Default")
      (node (ref "LED12") (pin "3") (pinfunction "DO_3") (pintype "output"))
      (node (ref "LED14") (pin "1") (pinfunction "DI_1") (pintype "input"))
    )
    (net (code "62") (name "Net-(LED15-DI)") (class "Default")
      (node (ref "LED15") (pin "1") (pinfunction "DI_1") (pintype "input"))
      (node (ref "LED4") (pin "3") (pinfunction "DO_3") (pintype "output"))
    )
    (net (code "63") (name "Net-(LED15-DO)") (class "Default")
      (node (ref "LED15") (pin "3") (pinfunction "DO_3") (pintype "output"))
      (node (ref "LED16") (pin "1") (pinfunction "DI_1") (pintype "input"))
    )
    (net (code "64") (name "Net-(LED16-DO)") (class "Default")
      (node (ref "LED16") (pin "3") (pinfunction "DO_3") (pintype "output"))
      (node (ref "LED17") (pin "1") (pinfunction "DI_1") (pintype "input"))
    )
    (net (code "65") (name "Net-(LED17-DO)") (class "Default")
      (node (ref "LED17") (pin "3") (pinfunction "DO_3") (pintype "output"))
      (node (ref "LED18") (pin "1") (pinfunction "DI_1") (pintype "input"))
    )
    (net (code "66") (name "Net-(LED18-DO)") (class "Default")
      (node (ref "LED18") (pin "3") (pinfunction "DO_3") (pintype "output"))
      (node (ref "LED19") (pin "1") (pinfunction "DI_1") (pintype "input"))
    )
    (net (code "67") (name "Net-(S1-Pad2)") (class "Default")
      (node (ref "S1") (pin "2") (pinfunction "2_2") (pintype "bidirectional"))
      (node (ref "U$5") (pin "+") (pinfunction "+_+") (pintype "bidirectional"))
    )
    (net (code "68") (name "Net-(U$6-D+)") (class "Default")
      (node (ref "R15") (pin "2") (pinfunction "2_2") (pintype "passive"))
      (node (ref "U$6") (pin "3") (pinfunction "D+_3") (pintype "bidirectional"))
    )
    (net (code "69") (name "Net-(U$6-D-)") (class "Default")
      (node (ref "R14") (pin "2") (pinfunction "2_2") (pintype "passive"))
      (node (ref "U$6") (pin "2") (pinfunction "D-_2") (pintype "bidirectional"))
    )
    (net (code "70") (name "Net-(U$6-VCC)") (class "Default")
      (node (ref "D5") (pin "A") (pinfunction "A_A") (pintype "passive"))
      (node (ref "U$6") (pin "1") (pinfunction "VCC_1") (pintype "bidirectional"))
    )
    (net (code "71") (name "Net-(U$10-ILIM)") (class "Default")
      (node (ref "R13") (pin "1") (pinfunction "1_1") (pintype "passive"))
      (node (ref "U$10") (pin "4") (pinfunction "ILIM_4") (pintype "bidirectional"))
    )
    (net (code "72") (name "Net-(U$10-STAT)") (class "Default")
      (node (ref "R12") (pin "2") (pinfunction "2_2") (pintype "passive"))
      (node (ref "U$10") (pin "1") (pinfunction "STAT_1") (pintype "bidirectional"))
    )
    (net (code "73") (name "Net-(U$10-VSNS)") (class "Default")
      (node (ref "R11") (pin "2") (pinfunction "2_2") (pintype "passive"))
      (node (ref "U$10") (pin "3") (pinfunction "VSNS_3") (pintype "bidirectional"))
    )
    (net (code "74") (name "Net-(U$10-~{EN})") (class "Default")
      (node (ref "R2") (pin "2") (pinfunction "2_2") (pintype "passive"))
      (node (ref "U$10") (pin "2") (pinfunction "~{EN}_2") (pintype "bidirectional"))
    )
    (net (code "75") (name "Net-(U$11-ANT)") (class "Default")
      (node (ref "JP1") (pin "1") (pinfunction "1_1") (pintype "passive"))
      (node (ref "U$11") (pin "B8") (pinfunction "ANT_B8") (pintype "passive"))
    )
    (net (code "76") (name "Net-(U1-FB)") (class "Default")
      (node (ref "C7") (pin "2") (pinfunction "2_2") (pintype "passive"))
      (node (ref "R6") (pin "1") (pinfunction "1_1") (pintype "passive"))
      (node (ref "R7") (pin "2") (pinfunction "2_2") (pintype "passive"))
      (node (ref "U1") (pin "3") (pinfunction "FB_3") (pintype "bidirectional"))
    )
    (net (code "77") (name "Net-(U2-32K_XN(GPIO33{slash}ADC1:5{slash}TOUCH8{slash}RTC8))") (class "Default")
      (node (ref "C14") (pin "1") (pinfunction "1_1") (pintype "passive"))
      (node (ref "U2") (pin "13") (pinfunction "32K_XN(GPIO33/ADC1:5/TOUCH8/RTC8)_13") (pintype "bidirectional"))
      (node (ref "X2") (pin "P$1") (pinfunction "P$1_P$1") (pintype "bidirectional"))
    )
    (net (code "78") (name "Net-(U2-32K_XP(GPIO32{slash}ADC1:4{slash}TOUCH9{slash}RTC9))") (class "Default")
      (node (ref "C15") (pin "2") (pinfunction "2_2") (pintype "passive"))
      (node (ref "U2") (pin "12") (pinfunction "32K_XP(GPIO32/ADC1:4/TOUCH9/RTC9)_12") (pintype "bidirectional"))
      (node (ref "X2") (pin "P$2") (pinfunction "P$2_P$2") (pintype "bidirectional"))
    )
    (net (code "79") (name "Net-(U2-CAP1)") (class "Default")
      (node (ref "C19") (pin "2") (pinfunction "2_2") (pintype "passive"))
      (node (ref "C20") (pin "1") (pinfunction "1_1") (pintype "passive"))
      (node (ref "R9") (pin "2") (pinfunction "2_2") (pintype "passive"))
      (node (ref "U2") (pin "48") (pinfunction "CAP1_48") (pintype "bidirectional"))
    )
    (net (code "80") (name "Net-(U2-CAP2)") (class "Default")
      (node (ref "C19") (pin "1") (pinfunction "1_1") (pintype "passive"))
      (node (ref "R9") (pin "1") (pinfunction "1_1") (pintype "passive"))
      (node (ref "U2") (pin "47") (pinfunction "CAP2_47") (pintype "bidirectional"))
    )
    (net (code "81") (name "Net-(U2-CHIP_PU)") (class "Default")
      (node (ref "R8") (pin "2") (pinfunction "2_2") (pintype "passive"))
      (node (ref "U2") (pin "9") (pinfunction "CHIP_PU_9") (pintype "bidirectional"))
    )
    (net (code "82") (name "Net-(U2-LNA_IN)") (class "Default")
      (node (ref "C11") (pin "2") (pinfunction "2_2") (pintype "passive"))
      (node (ref "L2") (pin "1") (pinfunction "1_1") (pintype "passive"))
      (node (ref "U2") (pin "2") (pinfunction "LNA_IN_2") (pintype "bidirectional"))
    )
    (net (code "83") (name "Net-(U2-SENSOR_CAPN(GPI38{slash}ADC1:2{slash}RTC2))") (class "Default")
      (node (ref "C17") (pin "2") (pinfunction "2_2") (pintype "passive"))
      (node (ref "U2") (pin "7") (pinfunction "SENSOR_CAPN(GPI38/ADC1:2/RTC2)_7") (pintype "bidirectional"))
    )
    (net (code "84") (name "Net-(U2-SENSOR_CAPP(GPI37{slash}ADC1:1{slash}RTC1))") (class "Default")
      (node (ref "C18") (pin "1") (pinfunction "1_1") (pintype "passive"))
      (node (ref "U2") (pin "6") (pinfunction "SENSOR_CAPP(GPI37/ADC1:1/RTC1)_6") (pintype "bidirectional"))
    )
    (net (code "85") (name "Net-(U2-SENSOR_VN(GPI39{slash}ADC1:3{slash}RTC3))") (class "Default")
      (node (ref "C17") (pin "1") (pinfunction "1_1") (pintype "passive"))
      (node (ref "U2") (pin "8") (pinfunction "SENSOR_VN(GPI39/ADC1:3/RTC3)_8") (pintype "bidirectional"))
    )
    (net (code "86") (name "Net-(U2-SENSOR_VP(GPI36{slash}ADC1:0{slash}RTC0))") (class "Default")
      (node (ref "C18") (pin "2") (pinfunction "2_2") (pintype "passive"))
      (node (ref "U2") (pin "5") (pinfunction "SENSOR_VP(GPI36/ADC1:0/RTC0)_5") (pintype "bidirectional"))
    )
    (net (code "87") (name "Net-(U2-XTAL_N)") (class "Default")
      (node (ref "C13") (pin "1") (pinfunction "1_1") (pintype "passive"))
      (node (ref "U2") (pin "44") (pinfunction "XTAL_N_44") (pintype "bidirectional"))
      (node (ref "Y2") (pin "3") (pinfunction "2_3") (pintype "passive"))
    )
    (net (code "88") (name "Net-(U2-XTAL_P)") (class "Default")
      (node (ref "C16") (pin "2") (pinfunction "2_2") (pintype "passive"))
      (node (ref "U2") (pin "45") (pinfunction "XTAL_P_45") (pintype "bidirectional"))
      (node (ref "Y2") (pin "1") (pinfunction "1_1") (pintype "passive"))
    )
    (net (code "89") (name "Net-(U4-AREF)") (class "Default")
      (node (ref "C5") (pin "1") (pinfunction "1_1") (pintype "passive"))
      (node (ref "U4") (pin "42") (pinfunction "AREF_42") (pintype "bidirectional"))
    )
    (net (code "90") (name "Net-(U4-UCAP)") (class "Default")
      (node (ref "C1") (pin "1") (pinfunction "1_1") (pintype "passive"))
      (node (ref "U4") (pin "6") (pinfunction "UCAP_6") (pintype "bidirectional"))
    )
    (net (code "91") (name "Net-(U4-XTAL1)") (class "Default")
      (node (ref "C3") (pin "2") (pinfunction "2_2") (pintype "passive"))
      (node (ref "U4") (pin "17") (pinfunction "XTAL1_17") (pintype "bidirectional"))
      (node (ref "Y1") (pin "3") (pinfunction "2_3") (pintype "passive"))
    )
    (net (code "92") (name "Net-(U4-XTAL2)") (class "Default")
      (node (ref "C2") (pin "1") (pinfunction "1_1") (pintype "passive"))
      (node (ref "U4") (pin "16") (pinfunction "XTAL2_16") (pintype "bidirectional"))
      (node (ref "Y1") (pin "1") (pinfunction "1_1") (pintype "passive"))
    )
    (net (code "93") (name "Net-(U4-~{RESET})") (class "Default")
      (node (ref "R3") (pin "1") (pinfunction "1_1") (pintype "passive"))
      (node (ref "U4") (pin "13") (pinfunction "~{RESET}_13") (pintype "bidirectional"))
    )
    (net (code "94") (name "unconnected-(FTDI-CTS-Pad5)") (class "Default")
      (node (ref "FTDI") (pin "5") (pinfunction "CTS_5") (pintype "passive"))
    )
    (net (code "95") (name "unconnected-(FTDI-DTR-Pad1)") (class "Default")
      (node (ref "FTDI") (pin "1") (pinfunction "DTR_1") (pintype "passive"))
    )
    (net (code "96") (name "unconnected-(JP2-Pad5)") (class "Default")
      (node (ref "JP2") (pin "5") (pinfunction "5_5") (pintype "passive"))
    )
    (net (code "97") (name "unconnected-(JP2-Pad6)") (class "Default")
      (node (ref "JP2") (pin "6") (pinfunction "6_6") (pintype "passive"))
    )
    (net (code "98") (name "unconnected-(LCD1-BS2-Pad6)") (class "Default")
      (node (ref "LCD1") (pin "6") (pinfunction "BS2_6") (pintype "bidirectional"))
    )
    (net (code "99") (name "unconnected-(LCD1-D2-Pad15)") (class "Default")
      (node (ref "LCD1") (pin "15") (pinfunction "D2_15") (pintype "bidirectional"))
    )
    (net (code "100") (name "unconnected-(LCD1-D3-Pad16)") (class "Default")
      (node (ref "LCD1") (pin "16") (pinfunction "D3_16") (pintype "bidirectional"))
    )
    (net (code "101") (name "unconnected-(LCD1-D4-Pad17)") (class "Default")
      (node (ref "LCD1") (pin "17") (pinfunction "D4_17") (pintype "bidirectional"))
    )
    (net (code "102") (name "unconnected-(LCD1-D5-Pad18)") (class "Default")
      (node (ref "LCD1") (pin "18") (pinfunction "D5_18") (pintype "bidirectional"))
    )
    (net (code "103") (name "unconnected-(LCD1-D6-Pad19)") (class "Default")
      (node (ref "LCD1") (pin "19") (pinfunction "D6_19") (pintype "bidirectional"))
    )
    (net (code "104") (name "unconnected-(LCD1-D7-Pad20)") (class "Default")
      (node (ref "LCD1") (pin "20") (pinfunction "D7_20") (pintype "bidirectional"))
    )
    (net (code "105") (name "unconnected-(LCD1-E-Pad12)") (class "Default")
      (node (ref "LCD1") (pin "12") (pinfunction "E_12") (pintype "bidirectional"))
    )
    (net (code "106") (name "unconnected-(LCD1-NC1-Pad1)") (class "Default")
      (node (ref "LCD1") (pin "1") (pinfunction "NC1_1") (pintype "no_connect"))
    )
    (net (code "107") (name "unconnected-(LCD1-NC2-Pad23)") (class "Default")
      (node (ref "LCD1") (pin "23") (pinfunction "NC2_23") (pintype "no_connect"))
    )
    (net (code "108") (name "unconnected-(LCD1-R{slash}W#-Pad11)") (class "Default")
      (node (ref "LCD1") (pin "11") (pinfunction "R/W#_11") (pintype "bidirectional"))
    )
    (net (code "109") (name "unconnected-(LED19-DO-Pad3)") (class "Default")
      (node (ref "LED19") (pin "3") (pinfunction "DO_3") (pintype "output"))
    )
    (net (code "110") (name "unconnected-(S1-Pad3)") (class "Default")
      (node (ref "S1") (pin "3") (pinfunction "3_3") (pintype "bidirectional"))
    )
    (net (code "111") (name "unconnected-(S1-Pad6)") (class "Default")
      (node (ref "S1") (pin "6") (pinfunction "6_6") (pintype "bidirectional"))
    )
    (net (code "112") (name "unconnected-(U$6-ID-Pad4)") (class "Default")
      (node (ref "U$6") (pin "4") (pinfunction "ID_4") (pintype "bidirectional"))
    )
    (net (code "113") (name "unconnected-(U$11-DIO1-PadB2)") (class "Default")
      (node (ref "U$11") (pin "B2") (pinfunction "DIO1_B2") (pintype "bidirectional"))
    )
    (net (code "114") (name "unconnected-(U$11-DIO2-PadB1)") (class "Default")
      (node (ref "U$11") (pin "B1") (pinfunction "DIO2_B1") (pintype "bidirectional"))
    )
    (net (code "115") (name "unconnected-(U$11-DIO3-PadB6)") (class "Default")
      (node (ref "U$11") (pin "B6") (pinfunction "DIO3_B6") (pintype "bidirectional"))
    )
    (net (code "116") (name "unconnected-(U$11-DIO4-PadB5)") (class "Default")
      (node (ref "U$11") (pin "B5") (pinfunction "DIO4_B5") (pintype "bidirectional"))
    )
    (net (code "117") (name "unconnected-(U$11-DIO5-PadA7)") (class "Default")
      (node (ref "U$11") (pin "A7") (pinfunction "DIO5_A7") (pintype "bidirectional"))
    )
    (net (code "118") (name "unconnected-(U2-VDD3P3_SDIO-Pad26)") (class "Default")
      (node (ref "U2") (pin "26") (pinfunction "VDD3P3_SDIO_26") (pintype "bidirectional"))
    )
    (net (code "119") (name "unconnected-(U2-VDET_1(GPI34{slash}ADC1:6)-Pad10)") (class "Default")
      (node (ref "U2") (pin "10") (pinfunction "VDET_1(GPI34/ADC1:6)_10") (pintype "bidirectional"))
    )
    (net (code "120") (name "unconnected-(U2-VDET_2(GPI35{slash}ADC1:7)-Pad11)") (class "Default")
      (node (ref "U2") (pin "11") (pinfunction "VDET_2(GPI35/ADC1:7)_11") (pintype "bidirectional"))
    )
    (net (code "121") (name "unconnected-(U4-PB0(SS)-Pad11)") (class "Default")
      (node (ref "U4") (pin "11") (pinfunction "PB0(SS)_11") (pintype "bidirectional"))
    )
    (net (code "122") (name "unconnected-(U4-PB1(SCK)-Pad9)") (class "Default")
      (node (ref "U4") (pin "9") (pinfunction "PB1(SCK)_9") (pintype "bidirectional"))
    )
    (net (code "123") (name "unconnected-(U4-PB2(MOSI)-Pad10)") (class "Default")
      (node (ref "U4") (pin "10") (pinfunction "PB2(MOSI)_10") (pintype "bidirectional"))
    )
    (net (code "124") (name "unconnected-(U4-PB3(MISO)-Pad8)") (class "Default")
      (node (ref "U4") (pin "8") (pinfunction "PB3(MISO)_8") (pintype "bidirectional"))
    )
    (net (code "125") (name "unconnected-(U4-PB4(ADC11)-Pad28)") (class "Default")
      (node (ref "U4") (pin "28") (pinfunction "PB4(ADC11)_28") (pintype "bidirectional"))
    )
    (net (code "126") (name "unconnected-(U4-PB5(ADC12)-Pad29)") (class "Default")
      (node (ref "U4") (pin "29") (pinfunction "PB5(ADC12)_29") (pintype "bidirectional"))
    )
    (net (code "127") (name "unconnected-(U4-PB6(ADC13)-Pad30)") (class "Default")
      (node (ref "U4") (pin "30") (pinfunction "PB6(ADC13)_30") (pintype "bidirectional"))
    )
    (net (code "128") (name "unconnected-(U4-PB7-Pad12)") (class "Default")
      (node (ref "U4") (pin "12") (pinfunction "PB7_12") (pintype "bidirectional"))
    )
    (net (code "129") (name "unconnected-(U4-PC6-Pad31)") (class "Default")
      (node (ref "U4") (pin "31") (pinfunction "PC6_31") (pintype "bidirectional"))
    )
    (net (code "130") (name "unconnected-(U4-PC7-Pad32)") (class "Default")
      (node (ref "U4") (pin "32") (pinfunction "PC7_32") (pintype "bidirectional"))
    )
    (net (code "131") (name "unconnected-(U4-PD0(SCL)-Pad18)") (class "Default")
      (node (ref "U4") (pin "18") (pinfunction "PD0(SCL)_18") (pintype "bidirectional"))
    )
    (net (code "132") (name "unconnected-(U4-PD1(SDA)-Pad19)") (class "Default")
      (node (ref "U4") (pin "19") (pinfunction "PD1(SDA)_19") (pintype "bidirectional"))
    )
    (net (code "133") (name "unconnected-(U4-PD4(ADC8)-Pad25)") (class "Default")
      (node (ref "U4") (pin "25") (pinfunction "PD4(ADC8)_25") (pintype "bidirectional"))
    )
    (net (code "134") (name "unconnected-(U4-PD5-Pad22)") (class "Default")
      (node (ref "U4") (pin "22") (pinfunction "PD5_22") (pintype "bidirectional"))
    )
    (net (code "135") (name "unconnected-(U4-PD6(ADC9)-Pad26)") (class "Default")
      (node (ref "U4") (pin "26") (pinfunction "PD6(ADC9)_26") (pintype "bidirectional"))
    )
    (net (code "136") (name "unconnected-(U4-PD7(ADC10)-Pad27)") (class "Default")
      (node (ref "U4") (pin "27") (pinfunction "PD7(ADC10)_27") (pintype "bidirectional"))
    )
    (net (code "137") (name "unconnected-(U4-PF0(ADC0)-Pad41)") (class "Default")
      (node (ref "U4") (pin "41") (pinfunction "PF0(ADC0)_41") (pintype "bidirectional"))
    )
    (net (code "138") (name "unconnected-(U4-PF1(ADC1)-Pad40)") (class "Default")
      (node (ref "U4") (pin "40") (pinfunction "PF1(ADC1)_40") (pintype "bidirectional"))
    )
    (net (code "139") (name "unconnected-(U4-PF4(ADC4)-Pad39)") (class "Default")
      (node (ref "U4") (pin "39") (pinfunction "PF4(ADC4)_39") (pintype "bidirectional"))
    )
    (net (code "140") (name "unconnected-(U4-PF5(ADC5)-Pad38)") (class "Default")
      (node (ref "U4") (pin "38") (pinfunction "PF5(ADC5)_38") (pintype "bidirectional"))
    )
    (net (code "141") (name "unconnected-(U4-PF6(ADC6)-Pad37)") (class "Default")
      (node (ref "U4") (pin "37") (pinfunction "PF6(ADC6)_37") (pintype "bidirectional"))
    )
    (net (code "142") (name "unconnected-(U4-PF7(ADC7)-Pad36)") (class "Default")
      (node (ref "U4") (pin "36") (pinfunction "PF7(ADC7)_36") (pintype "bidirectional"))
    )
  )
)
